# wifi.net
KiCad netlist of a schematic drawn in EAGLE
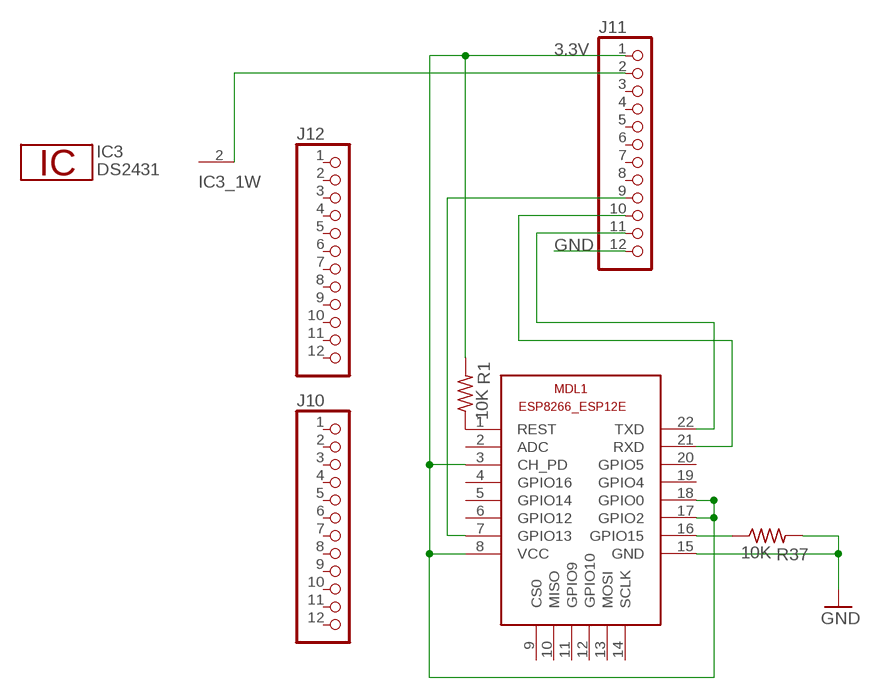
[diagram p0: schematic, sheet 1]

(export (version "E")
  (design (tool "Eeschema 10.0.6"))
  (components
    (comp (ref "IC3")
      (value "DS2431")
      (footprint "eagle-import:TO92-")
      (libsource (lib "eagle-import") (part "DS2431"))
    )
    (comp (ref "J10")
      (value "PINHD-1X12")
      (footprint "eagle-import:1X12")
      (libsource (lib "eagle-import") (part "PINHD-1X12"))
    )
    (comp (ref "J11")
      (value "PINHD-1X12")
      (footprint "eagle-import:1X12")
      (libsource (lib "eagle-import") (part "PINHD-1X12"))
    )
    (comp (ref "J12")
      (value "PINHD-1X12")
      (footprint "eagle-import:1X12")
      (libsource (lib "eagle-import") (part "PINHD-1X12"))
    )
    (comp (ref "MDL1")
      (value "ESP8266-12EESP8266-ESP12E")
      (footprint "eagle-import:ESP8266-ESP12E")
      (libsource (lib "eagle-import") (part "ESP8266-12EESP8266-ESP12E"))
    )
    (comp (ref "R1")
      (value "10K")
      (footprint "eagle-import:R0805")
      (libsource (lib "eagle-import") (part "R-US_R0805"))
    )
    (comp (ref "R37")
      (value "10K")
      (footprint "eagle-import:R0805")
      (libsource (lib "eagle-import") (part "R-US_R0805"))
    )
  )
  (nets
    (net (code "1") (name "/3.3V") (class "Default")
      (node (ref "J11") (pin "1") (pinfunction "1_1") (pintype "passive"))
      (node (ref "MDL1") (pin "17") (pinfunction "GPIO2_17") (pintype "bidirectional"))
      (node (ref "MDL1") (pin "18") (pinfunction "GPIO0_18") (pintype "bidirectional"))
      (node (ref "MDL1") (pin "3") (pinfunction "CH_PD_3") (pintype "bidirectional"))
      (node (ref "MDL1") (pin "8") (pinfunction "VCC_8") (pintype "bidirectional"))
      (node (ref "R1") (pin "2") (pinfunction "2_2") (pintype "passive"))
    )
    (net (code "2") (name "GND") (class "Default")
      (node (ref "J11") (pin "12") (pinfunction "12_12") (pintype "passive"))
      (node (ref "MDL1") (pin "15") (pinfunction "GND_15") (pintype "bidirectional"))
      (node (ref "R37") (pin "2") (pinfunction "2_2") (pintype "passive"))
    )
    (net (code "3") (name "Net-(IC3C-1W)") (class "Default")
      (node (ref "IC3") (pin "2") (pinfunction "1W_2") (pintype "power_in"))
      (node (ref "J11") (pin "2") (pinfunction "2_2") (pintype "passive"))
    )
    (net (code "4") (name "Net-(MDL1-GPIO13)") (class "Default")
      (node (ref "J11") (pin "9") (pinfunction "9_9") (pintype "passive"))
      (node (ref "MDL1") (pin "7") (pinfunction "GPIO13_7") (pintype "bidirectional"))
    )
    (net (code "5") (name "Net-(MDL1-GPIO15)") (class "Default")
      (node (ref "MDL1") (pin "16") (pinfunction "GPIO15_16") (pintype "bidirectional"))
      (node (ref "R37") (pin "1") (pinfunction "1_1") (pintype "passive"))
    )
    (net (code "6") (name "Net-(MDL1-REST)") (class "Default")
      (node (ref "MDL1") (pin "1") (pinfunction "REST_1") (pintype "bidirectional"))
      (node (ref "R1") (pin "1") (pinfunction "1_1") (pintype "passive"))
    )
    (net (code "7") (name "Net-(MDL1-RXD)") (class "Default")
      (node (ref "J11") (pin "10") (pinfunction "10_10") (pintype "passive"))
      (node (ref "MDL1") (pin "21") (pinfunction "RXD_21") (pintype "bidirectional"))
    )
    (net (code "8") (name "Net-(MDL1-TXD)") (class "Default")
      (node (ref "J11") (pin "11") (pinfunction "11_11") (pintype "passive"))
      (node (ref "MDL1") (pin "22") (pinfunction "TXD_22") (pintype "bidirectional"))
    )
    (net (code "9") (name "unconnected-(J10-Pad1)") (class "Default")
      (node (ref "J10") (pin "1") (pinfunction "1_1") (pintype "passive"))
    )
    (net (code "10") (name "unconnected-(J10-Pad2)") (class "Default")
      (node (ref "J10") (pin "2") (pinfunction "2_2") (pintype "passive"))
    )
    (net (code "11") (name "unconnected-(J10-Pad3)") (class "Default")
      (node (ref "J10") (pin "3") (pinfunction "3_3") (pintype "passive"))
    )
    (net (code "12") (name "unconnected-(J10-Pad4)") (class "Default")
      (node (ref "J10") (pin "4") (pinfunction "4_4") (pintype "passive"))
    )
    (net (code "13") (name "unconnected-(J10-Pad5)") (class "Default")
      (node (ref "J10") (pin "5") (pinfunction "5_5") (pintype "passive"))
    )
    (net (code "14") (name "unconnected-(J10-Pad6)") (class "Default")
      (node (ref "J10") (pin "6") (pinfunction "6_6") (pintype "passive"))
    )
    (net (code "15") (name "unconnected-(J10-Pad7)") (class "Default")
      (node (ref "J10") (pin "7") (pinfunction "7_7") (pintype "passive"))
    )
    (net (code "16") (name "unconnected-(J10-Pad8)") (class "Default")
      (node (ref "J10") (pin "8") (pinfunction "8_8") (pintype "passive"))
    )
    (net (code "17") (name "unconnected-(J10-Pad9)") (class "Default")
      (node (ref "J10") (pin "9") (pinfunction "9_9") (pintype "passive"))
    )
    (net (code "18") (name "unconnected-(J10-Pad10)") (class "Default")
      (node (ref "J10") (pin "10") (pinfunction "10_10") (pintype "passive"))
    )
    (net (code "19") (name "unconnected-(J10-Pad11)") (class "Default")
      (node (ref "J10") (pin "11") (pinfunction "11_11") (pintype "passive"))
    )
    (net (code "20") (name "unconnected-(J10-Pad12)") (class "Default")
      (node (ref "J10") (pin "12") (pinfunction "12_12") (pintype "passive"))
    )
    (net (code "21") (name "unconnected-(J11-Pad3)") (class "Default")
      (node (ref "J11") (pin "3") (pinfunction "3_3") (pintype "passive"))
    )
    (net (code "22") (name "unconnected-(J11-Pad4)") (class "Default")
      (node (ref "J11") (pin "4") (pinfunction "4_4") (pintype "passive"))
    )
    (net (code "23") (name "unconnected-(J11-Pad5)") (class "Default")
      (node (ref "J11") (pin "5") (pinfunction "5_5") (pintype "passive"))
    )
    (net (code "24") (name "unconnected-(J11-Pad6)") (class "Default")
      (node (ref "J11") (pin "6") (pinfunction "6_6") (pintype "passive"))
    )
    (net (code "25") (name "unconnected-(J11-Pad7)") (class "Default")
      (node (ref "J11") (pin "7") (pinfunction "7_7") (pintype "passive"))
    )
    (net (code "26") (name "unconnected-(J11-Pad8)") (class "Default")
      (node (ref "J11") (pin "8") (pinfunction "8_8") (pintype "passive"))
    )
    (net (code "27") (name "unconnected-(J12-Pad1)") (class "Default")
      (node (ref "J12") (pin "1") (pinfunction "1_1") (pintype "passive"))
    )
    (net (code "28") (name "unconnected-(J12-Pad2)") (class "Default")
      (node (ref "J12") (pin "2") (pinfunction "2_2") (pintype "passive"))
    )
    (net (code "29") (name "unconnected-(J12-Pad3)") (class "Default")
      (node (ref "J12") (pin "3") (pinfunction "3_3") (pintype "passive"))
    )
    (net (code "30") (name "unconnected-(J12-Pad4)") (class "Default")
      (node (ref "J12") (pin "4") (pinfunction "4_4") (pintype "passive"))
    )
    (net (code "31") (name "unconnected-(J12-Pad5)") (class "Default")
      (node (ref "J12") (pin "5") (pinfunction "5_5") (pintype "passive"))
    )
    (net (code "32") (name "unconnected-(J12-Pad6)") (class "Default")
      (node (ref "J12") (pin "6") (pinfunction "6_6") (pintype "passive"))
    )
    (net (code "33") (name "unconnected-(J12-Pad7)") (class "Default")
      (node (ref "J12") (pin "7") (pinfunction "7_7") (pintype "passive"))
    )
    (net (code "34") (name "unconnected-(J12-Pad8)") (class "Default")
      (node (ref "J12") (pin "8") (pinfunction "8_8") (pintype "passive"))
    )
    (net (code "35") (name "unconnected-(J12-Pad9)") (class "Default")
      (node (ref "J12") (pin "9") (pinfunction "9_9") (pintype "passive"))
    )
    (net (code "36") (name "unconnected-(J12-Pad10)") (class "Default")
      (node (ref "J12") (pin "10") (pinfunction "10_10") (pintype "passive"))
    )
    (net (code "37") (name "unconnected-(J12-Pad11)") (class "Default")
      (node (ref "J12") (pin "11") (pinfunction "11_11") (pintype "passive"))
    )
    (net (code "38") (name "unconnected-(J12-Pad12)") (class "Default")
      (node (ref "J12") (pin "12") (pinfunction "12_12") (pintype "passive"))
    )
    (net (code "39") (name "unconnected-(MDL1-ADC-Pad2)") (class "Default")
      (node (ref "MDL1") (pin "2") (pinfunction "ADC_2") (pintype "bidirectional"))
    )
    (net (code "40") (name "unconnected-(MDL1-CS0-Pad9)") (class "Default")
      (node (ref "MDL1") (pin "9") (pinfunction "CS0_9") (pintype "bidirectional"))
    )
    (net (code "41") (name "unconnected-(MDL1-GPIO4-Pad19)") (class "Default")
      (node (ref "MDL1") (pin "19") (pinfunction "GPIO4_19") (pintype "bidirectional"))
    )
    (net (code "42") (name "unconnected-(MDL1-GPIO5-Pad20)") (class "Default")
      (node (ref "MDL1") (pin "20") (pinfunction "GPIO5_20") (pintype "bidirectional"))
    )
    (net (code "43") (name "unconnected-(MDL1-GPIO9-Pad11)") (class "Default")
      (node (ref "MDL1") (pin "11") (pinfunction "GPIO9_11") (pintype "bidirectional"))
    )
    (net (code "44") (name "unconnected-(MDL1-GPIO10-Pad12)") (class "Default")
      (node (ref "MDL1") (pin "12") (pinfunction "GPIO10_12") (pintype "bidirectional"))
    )
    (net (code "45") (name "unconnected-(MDL1-GPIO12-Pad6)") (class "Default")
      (node (ref "MDL1") (pin "6") (pinfunction "GPIO12_6") (pintype "bidirectional"))
    )
    (net (code "46") (name "unconnected-(MDL1-GPIO14-Pad5)") (class "Default")
      (node (ref "MDL1") (pin "5") (pinfunction "GPIO14_5") (pintype "bidirectional"))
    )
    (net (code "47") (name "unconnected-(MDL1-GPIO16-Pad4)") (class "Default")
      (node (ref "MDL1") (pin "4") (pinfunction "GPIO16_4") (pintype "bidirectional"))
    )
    (net (code "48") (name "unconnected-(MDL1-MISO-Pad10)") (class "Default")
      (node (ref "MDL1") (pin "10") (pinfunction "MISO_10") (pintype "bidirectional"))
    )
    (net (code "49") (name "unconnected-(MDL1-MOSI-Pad13)") (class "Default")
      (node (ref "MDL1") (pin "13") (pinfunction "MOSI_13") (pintype "bidirectional"))
    )
    (net (code "50") (name "unconnected-(MDL1-SCLK-Pad14)") (class "Default")
      (node (ref "MDL1") (pin "14") (pinfunction "SCLK_14") (pintype "bidirectional"))
    )
  )
)
